# Current_Sensor_Board.net
KiCad netlist of a schematic drawn in EAGLE
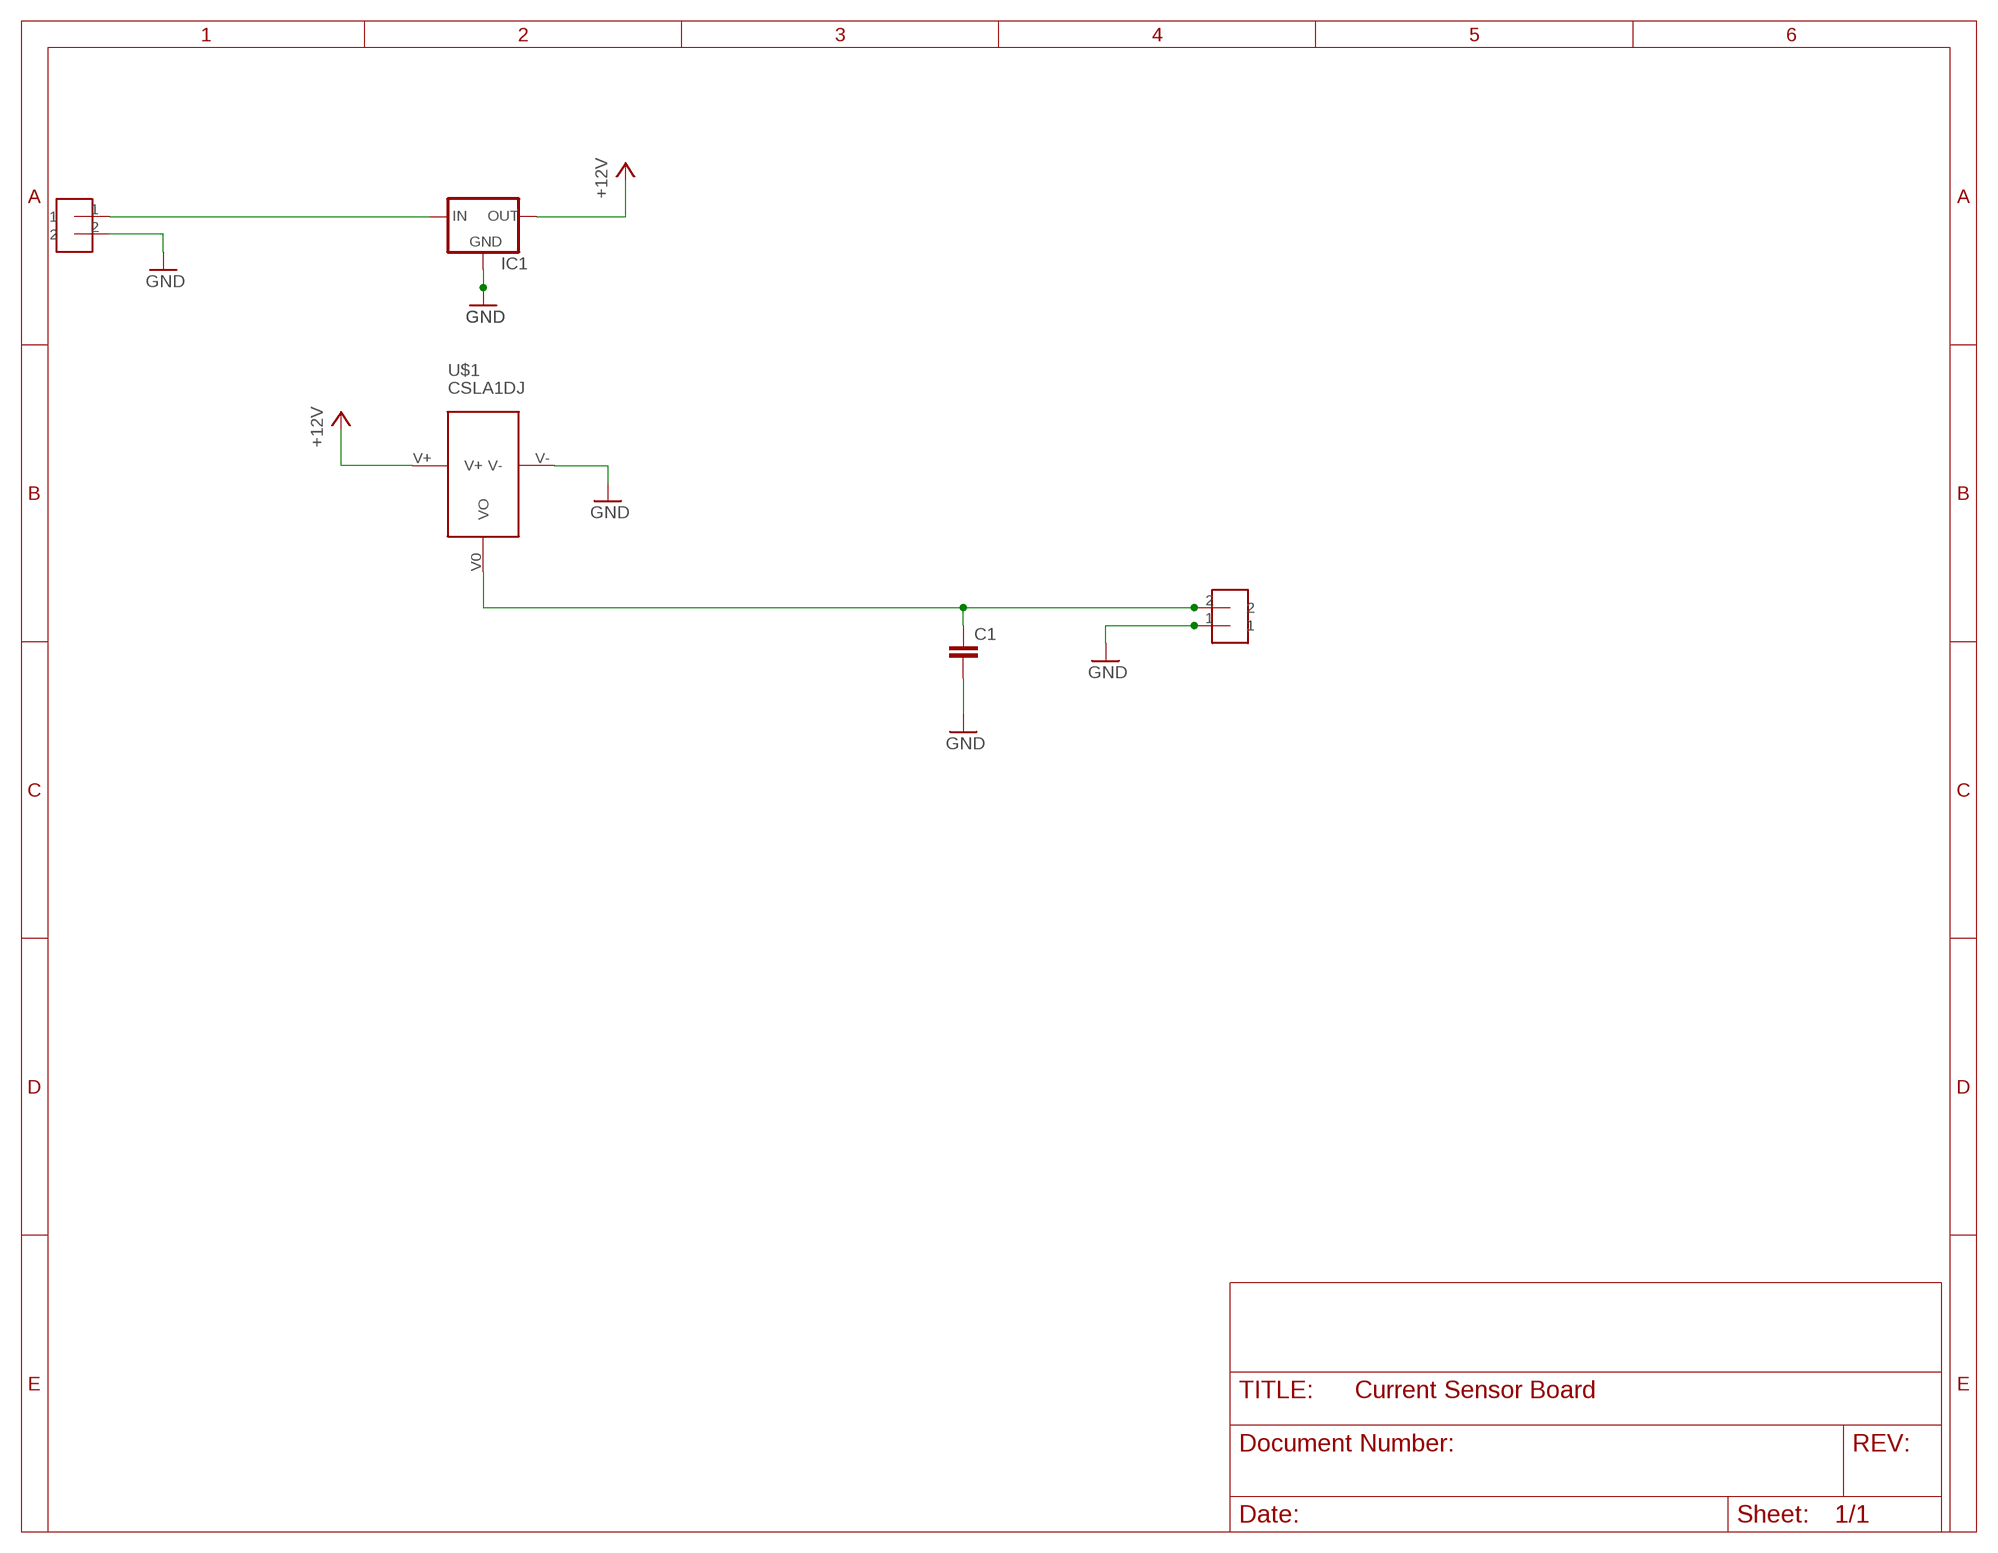
[diagram p0: schematic, sheet 1]

(export (version "E")
  (design (tool "Eeschema 10.0.6"))
  (components
    (comp (ref "C1")
      (value "C-EU050-050X075")
      (footprint "eagle-import:C050-050X075")
      (libsource (lib "eagle-import") (part "C-EU050-050X075"))
    )
    (comp (ref "IC1")
      (value "78XXS")
      (footprint "eagle-import:78XXS")
      (libsource (lib "eagle-import") (part "78XXS"))
    )
    (comp (ref "U$1")
      (value "CSLA1DJ")
      (footprint "eagle-import:CSLA1DJ")
      (libsource (lib "eagle-import") (part "CSLA1DJ"))
    )
    (comp (ref "U$2")
      (value "1X2HEADER_100MIL")
      (footprint "eagle-import:1X2_100MIL")
      (libsource (lib "eagle-import") (part "1X2HEADER_100MIL"))
    )
    (comp (ref "U$3")
      (value "1X2HEADER_100MIL")
      (footprint "eagle-import:1X2_100MIL")
      (libsource (lib "eagle-import") (part "1X2HEADER_100MIL"))
    )
  )
  (nets
    (net (code "1") (name "+12V") (class "Default")
      (node (ref "IC1") (pin "OUT") (pinfunction "OUT_OUT") (pintype "passive"))
      (node (ref "U$1") (pin "V+") (pinfunction "V+_V+") (pintype "bidirectional"))
    )
    (net (code "2") (name "GND") (class "Default")
      (node (ref "C1") (pin "2") (pinfunction "2_2") (pintype "passive"))
      (node (ref "IC1") (pin "GND") (pinfunction "GND_GND") (pintype "input"))
      (node (ref "U$1") (pin "V-") (pinfunction "V-_V-") (pintype "bidirectional"))
      (node (ref "U$2") (pin "1") (pinfunction "1_1") (pintype "bidirectional"))
      (node (ref "U$3") (pin "2") (pinfunction "2_2") (pintype "bidirectional"))
    )
    (net (code "3") (name "Net-(IC1-PadIN)") (class "Default")
      (node (ref "IC1") (pin "IN") (pinfunction "IN_IN") (pintype "input"))
      (node (ref "U$3") (pin "1") (pinfunction "1_1") (pintype "bidirectional"))
    )
    (net (code "4") (name "Net-(U$1-VO)") (class "Default")
      (node (ref "C1") (pin "1") (pinfunction "1_1") (pintype "passive"))
      (node (ref "U$1") (pin "V0") (pinfunction "VO_V0") (pintype "bidirectional"))
      (node (ref "U$2") (pin "2") (pinfunction "2_2") (pintype "bidirectional"))
    )
  )
)
